# 06_PWM_IO.net
KiCad netlist of a schematic drawn in Altium Designer
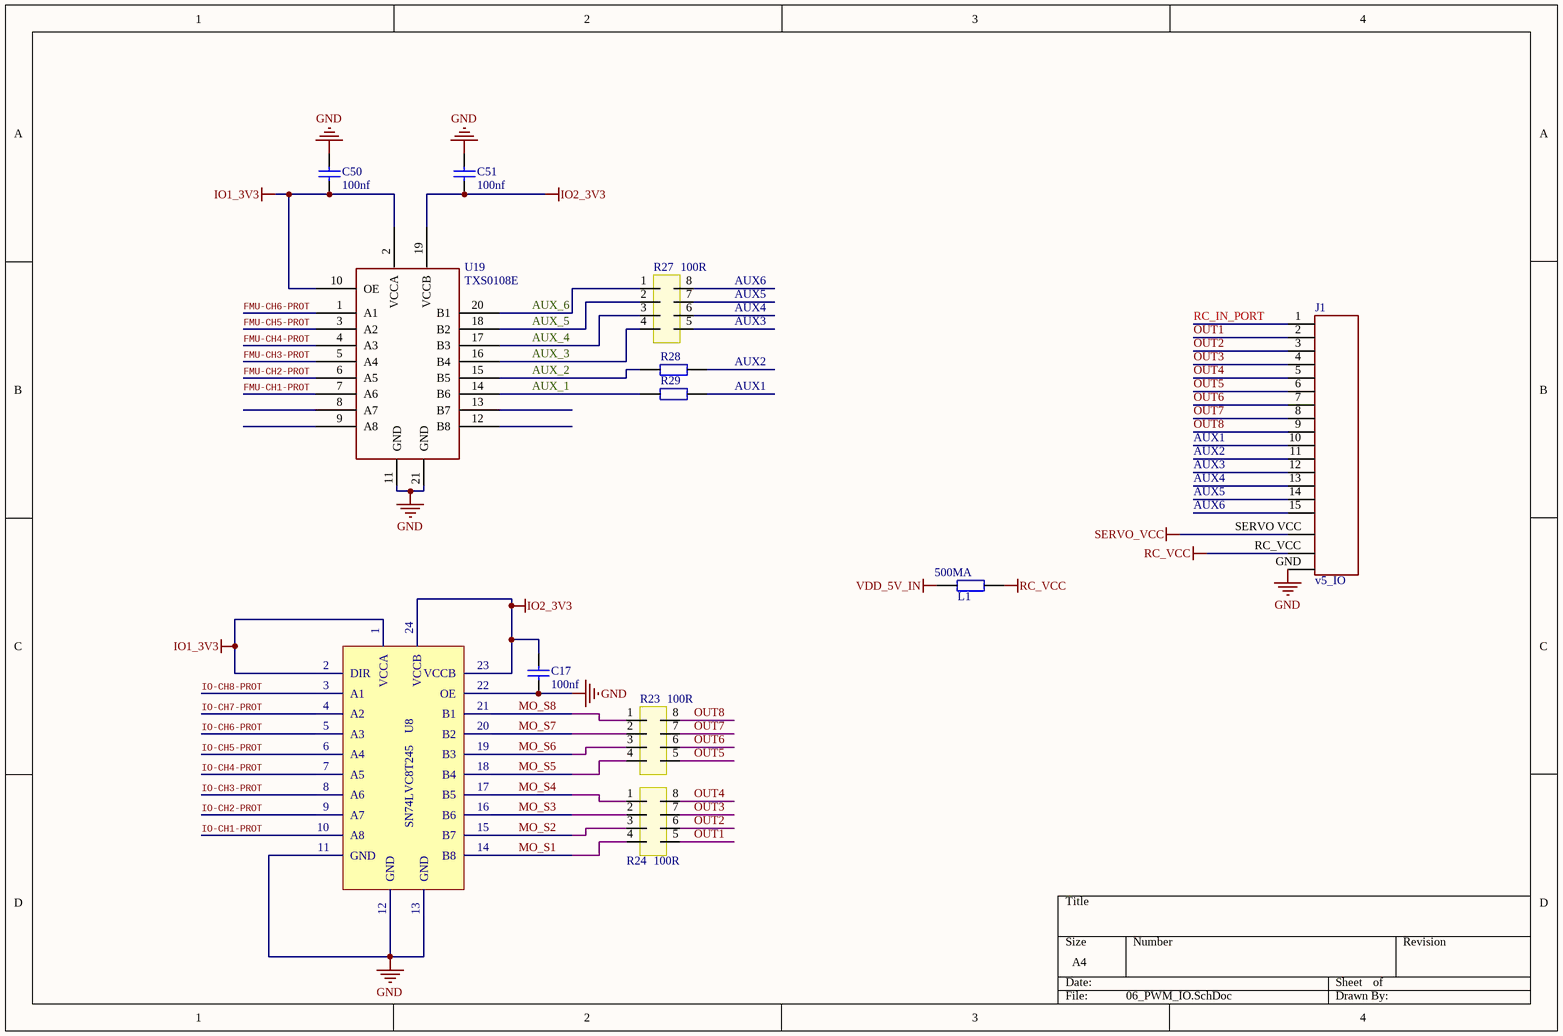
[diagram p0: 06_PWM_IO.SchDoc]

(export (version "E")
  (design (tool "Eeschema 10.0.6"))
  (components
    (comp (ref "C17")
      (value "100nf")
      (fields (field (name "PUBLISHER") "Altium Limited"))
      (libsource (lib "Miscellaneous Devices") (part "Cap"))
    )
    (comp (ref "C50") (value "100nf") (libsource (lib "Miscellaneous Devices") (part "Cap")))
    (comp (ref "C51") (value "100nf") (libsource (lib "Miscellaneous Devices") (part "Cap")))
    (comp (ref "J1") (value "v5_IO") (footprint "V5_IO_PWM") (libsource (lib "CUAV") (part "v5_IO")))
    (comp (ref "L1")
      (value "500MA")
      (footprint "0805l")
      (description "0402R100R 1%")
      (libsource (lib "CUAV") (part "0402R100R"))
    )
    (comp (ref "R23") (value "100R") (footprint "0402_4r") (libsource (lib "CUAV") (part "0402-8R-4R")))
    (comp (ref "R24") (value "100R") (footprint "0402_4r") (libsource (lib "CUAV") (part "0402-8R-4R")))
    (comp (ref "R27") (value "100R") (footprint "0402_4r") (libsource (lib "CUAV") (part "0402-8R-4R")))
    (comp (ref "R28")
      (value "0402R100R")
      (footprint "0402R")
      (description "0402R100R 1%")
      (libsource (lib "") (part "0402R100R_1"))
    )
    (comp (ref "R29")
      (value "0402R100R")
      (footprint "0402R")
      (description "0402R100R 1%")
      (libsource (lib "") (part "0402R100R_1"))
    )
    (comp (ref "U8")
      (value "SN74LVC8T245")
      (footprint "QFN24-RGY")
      (libsource (lib "CUAV") (part "SN74LVC8T245"))
    )
    (comp (ref "U19") (value "TXS0108E") (footprint "VQFN20") (libsource (lib "CUAV") (part "TXS0108E")))
  )
  (nets
    (net (code "1") (name "/AUX1") (class "Default")
      (node (ref "J1") (pin "10") (pintype "passive"))
      (node (ref "R29") (pin "2") (pintype "passive"))
    )
    (net (code "2") (name "/AUX2") (class "Default")
      (node (ref "J1") (pin "11") (pintype "passive"))
      (node (ref "R28") (pin "2") (pintype "passive"))
    )
    (net (code "3") (name "/AUX3") (class "Default")
      (node (ref "J1") (pin "12") (pintype "passive"))
      (node (ref "R27") (pin "5") (pinfunction "5_5") (pintype "passive"))
    )
    (net (code "4") (name "/AUX4") (class "Default")
      (node (ref "J1") (pin "13") (pintype "passive"))
      (node (ref "R27") (pin "6") (pinfunction "6_6") (pintype "passive"))
    )
    (net (code "5") (name "/AUX5") (class "Default")
      (node (ref "J1") (pin "14") (pintype "passive"))
      (node (ref "R27") (pin "7") (pinfunction "7_7") (pintype "passive"))
    )
    (net (code "6") (name "/AUX6") (class "Default")
      (node (ref "J1") (pin "15") (pintype "passive"))
      (node (ref "R27") (pin "8") (pinfunction "8_8") (pintype "passive"))
    )
    (net (code "7") (name "/AUX_1") (class "Default")
      (node (ref "R29") (pin "1") (pintype "passive"))
      (node (ref "U19") (pin "14") (pinfunction "B6_14") (pintype "passive"))
    )
    (net (code "8") (name "/AUX_2") (class "Default")
      (node (ref "R28") (pin "1") (pintype "passive"))
      (node (ref "U19") (pin "15") (pinfunction "B5_15") (pintype "passive"))
    )
    (net (code "9") (name "/AUX_3") (class "Default")
      (node (ref "R27") (pin "4") (pinfunction "4_4") (pintype "passive"))
      (node (ref "U19") (pin "16") (pinfunction "B4_16") (pintype "passive"))
    )
    (net (code "10") (name "/AUX_4") (class "Default")
      (node (ref "R27") (pin "3") (pinfunction "3_3") (pintype "passive"))
      (node (ref "U19") (pin "17") (pinfunction "B3_17") (pintype "passive"))
    )
    (net (code "11") (name "/AUX_5") (class "Default")
      (node (ref "R27") (pin "2") (pinfunction "2_2") (pintype "passive"))
      (node (ref "U19") (pin "18") (pinfunction "B2_18") (pintype "passive"))
    )
    (net (code "12") (name "/AUX_6") (class "Default")
      (node (ref "R27") (pin "1") (pinfunction "1_1") (pintype "passive"))
      (node (ref "U19") (pin "20") (pinfunction "B1_20") (pintype "passive"))
    )
    (net (code "13") (name "/FMU-CH1-PROT") (class "Default")
      (node (ref "U19") (pin "7") (pinfunction "A6_7") (pintype "passive"))
    )
    (net (code "14") (name "/FMU-CH2-PROT") (class "Default")
      (node (ref "U19") (pin "6") (pinfunction "A5_6") (pintype "passive"))
    )
    (net (code "15") (name "/FMU-CH3-PROT") (class "Default")
      (node (ref "U19") (pin "5") (pinfunction "A4_5") (pintype "passive"))
    )
    (net (code "16") (name "/FMU-CH4-PROT") (class "Default")
      (node (ref "U19") (pin "4") (pinfunction "A3_4") (pintype "passive"))
    )
    (net (code "17") (name "/FMU-CH5-PROT") (class "Default")
      (node (ref "U19") (pin "3") (pinfunction "A2_3") (pintype "passive"))
    )
    (net (code "18") (name "/FMU-CH6-PROT") (class "Default")
      (node (ref "U19") (pin "1") (pinfunction "A1_1") (pintype "passive"))
    )
    (net (code "19") (name "/IO-CH1-PROT") (class "Default")
      (node (ref "U8") (pin "10") (pinfunction "A8_10") (pintype "passive"))
    )
    (net (code "20") (name "/IO-CH2-PROT") (class "Default")
      (node (ref "U8") (pin "9") (pinfunction "A7_9") (pintype "passive"))
    )
    (net (code "21") (name "/IO-CH3-PROT") (class "Default")
      (node (ref "U8") (pin "8") (pinfunction "A6_8") (pintype "passive"))
    )
    (net (code "22") (name "/IO-CH4-PROT") (class "Default")
      (node (ref "U8") (pin "7") (pinfunction "A5_7") (pintype "passive"))
    )
    (net (code "23") (name "/IO-CH5-PROT") (class "Default")
      (node (ref "U8") (pin "6") (pinfunction "A4_6") (pintype "passive"))
    )
    (net (code "24") (name "/IO-CH6-PROT") (class "Default")
      (node (ref "U8") (pin "5") (pinfunction "A3_5") (pintype "passive"))
    )
    (net (code "25") (name "/IO-CH7-PROT") (class "Default")
      (node (ref "U8") (pin "4") (pinfunction "A2_4") (pintype "passive"))
    )
    (net (code "26") (name "/IO-CH8-PROT") (class "Default")
      (node (ref "U8") (pin "3") (pinfunction "A1_3") (pintype "passive"))
    )
    (net (code "27") (name "/MO_S1") (class "Default")
      (node (ref "R24") (pin "4") (pinfunction "4_4") (pintype "passive"))
      (node (ref "U8") (pin "14") (pinfunction "B8_14") (pintype "passive"))
    )
    (net (code "28") (name "/MO_S2") (class "Default")
      (node (ref "R24") (pin "3") (pinfunction "3_3") (pintype "passive"))
      (node (ref "U8") (pin "15") (pinfunction "B7_15") (pintype "passive"))
    )
    (net (code "29") (name "/MO_S3") (class "Default")
      (node (ref "R24") (pin "2") (pinfunction "2_2") (pintype "passive"))
      (node (ref "U8") (pin "16") (pinfunction "B6_16") (pintype "passive"))
    )
    (net (code "30") (name "/MO_S4") (class "Default")
      (node (ref "R24") (pin "1") (pinfunction "1_1") (pintype "passive"))
      (node (ref "U8") (pin "17") (pinfunction "B5_17") (pintype "passive"))
    )
    (net (code "31") (name "/MO_S5") (class "Default")
      (node (ref "R23") (pin "4") (pinfunction "4_4") (pintype "passive"))
      (node (ref "U8") (pin "18") (pinfunction "B4_18") (pintype "passive"))
    )
    (net (code "32") (name "/MO_S6") (class "Default")
      (node (ref "R23") (pin "3") (pinfunction "3_3") (pintype "passive"))
      (node (ref "U8") (pin "19") (pinfunction "B3_19") (pintype "passive"))
    )
    (net (code "33") (name "/MO_S7") (class "Default")
      (node (ref "R23") (pin "2") (pinfunction "2_2") (pintype "passive"))
      (node (ref "U8") (pin "20") (pinfunction "B2_20") (pintype "passive"))
    )
    (net (code "34") (name "/MO_S8") (class "Default")
      (node (ref "R23") (pin "1") (pinfunction "1_1") (pintype "passive"))
      (node (ref "U8") (pin "21") (pinfunction "B1_21") (pintype "passive"))
    )
    (net (code "35") (name "/OUT1") (class "Default")
      (node (ref "J1") (pin "2") (pintype "passive"))
      (node (ref "R24") (pin "5") (pinfunction "5_5") (pintype "passive"))
    )
    (net (code "36") (name "/OUT2") (class "Default")
      (node (ref "J1") (pin "3") (pintype "passive"))
      (node (ref "R24") (pin "6") (pinfunction "6_6") (pintype "passive"))
    )
    (net (code "37") (name "/OUT3") (class "Default")
      (node (ref "J1") (pin "4") (pintype "passive"))
      (node (ref "R24") (pin "7") (pinfunction "7_7") (pintype "passive"))
    )
    (net (code "38") (name "/OUT4") (class "Default")
      (node (ref "J1") (pin "5") (pintype "passive"))
      (node (ref "R24") (pin "8") (pinfunction "8_8") (pintype "passive"))
    )
    (net (code "39") (name "/OUT5") (class "Default")
      (node (ref "J1") (pin "6") (pintype "passive"))
      (node (ref "R23") (pin "5") (pinfunction "5_5") (pintype "passive"))
    )
    (net (code "40") (name "/OUT6") (class "Default")
      (node (ref "J1") (pin "7") (pintype "passive"))
      (node (ref "R23") (pin "6") (pinfunction "6_6") (pintype "passive"))
    )
    (net (code "41") (name "/OUT7") (class "Default")
      (node (ref "J1") (pin "8") (pintype "passive"))
      (node (ref "R23") (pin "7") (pinfunction "7_7") (pintype "passive"))
    )
    (net (code "42") (name "/OUT8") (class "Default")
      (node (ref "J1") (pin "9") (pintype "passive"))
      (node (ref "R23") (pin "8") (pinfunction "8_8") (pintype "passive"))
    )
    (net (code "43") (name "/RC_IN_PORT") (class "Default") (node (ref "J1") (pin "1") (pintype "passive")))
    (net (code "44") (name "GND") (class "Default")
      (node (ref "C17") (pin "1") (pinfunction "1_1") (pintype "passive"))
      (node (ref "C50") (pin "1") (pinfunction "1_1") (pintype "passive"))
      (node (ref "C51") (pin "1") (pinfunction "1_1") (pintype "passive"))
      (node (ref "J1") (pin "GND") (pintype "passive"))
      (node (ref "U19") (pin "11") (pinfunction "GND_11") (pintype "passive"))
      (node (ref "U19") (pin "21") (pinfunction "GND_21") (pintype "passive"))
      (node (ref "U8") (pin "11") (pinfunction "GND_11") (pintype "passive"))
      (node (ref "U8") (pin "12") (pinfunction "GND_12") (pintype "passive"))
      (node (ref "U8") (pin "13") (pinfunction "GND_13") (pintype "passive"))
      (node (ref "U8") (pin "22") (pinfunction "OE_22") (pintype "passive"))
    )
    (net (code "45") (name "IO1_3V3") (class "Default")
      (node (ref "C50") (pin "2") (pinfunction "2_2") (pintype "passive"))
      (node (ref "U19") (pin "10") (pinfunction "OE_10") (pintype "passive"))
      (node (ref "U19") (pin "2") (pinfunction "VCCA_2") (pintype "passive"))
      (node (ref "U8") (pin "1") (pinfunction "VCCA_1") (pintype "passive"))
      (node (ref "U8") (pin "2") (pinfunction "DIR_2") (pintype "passive"))
    )
    (net (code "46") (name "IO2_3V3") (class "Default")
      (node (ref "C17") (pin "2") (pinfunction "2_2") (pintype "passive"))
      (node (ref "C51") (pin "2") (pinfunction "2_2") (pintype "passive"))
      (node (ref "U19") (pin "19") (pinfunction "VCCB_19") (pintype "passive"))
      (node (ref "U8") (pin "23") (pinfunction "VCCB_23") (pintype "passive"))
      (node (ref "U8") (pin "24") (pinfunction "VCCB_24") (pintype "passive"))
    )
    (net (code "47") (name "RC_VCC") (class "Default")
      (node (ref "J1") (pin "RC_VCC") (pintype "passive"))
      (node (ref "L1") (pin "1") (pintype "passive"))
    )
    (net (code "48") (name "SERVO_VCC") (class "Default")
      (node (ref "J1") (pin "SERVO_VCC") (pintype "passive"))
    )
    (net (code "49") (name "VDD_5V_IN") (class "Default") (node (ref "L1") (pin "2") (pintype "passive")))
    (net (code "50") (name "unconnected-(U19-A7-Pad8)") (class "Default")
      (node (ref "U19") (pin "8") (pinfunction "A7_8") (pintype "passive"))
    )
    (net (code "51") (name "unconnected-(U19-A8-Pad9)") (class "Default")
      (node (ref "U19") (pin "9") (pinfunction "A8_9") (pintype "passive"))
    )
    (net (code "52") (name "unconnected-(U19-B7-Pad13)") (class "Default")
      (node (ref "U19") (pin "13") (pinfunction "B7_13") (pintype "passive"))
    )
    (net (code "53") (name "unconnected-(U19-B8-Pad12)") (class "Default")
      (node (ref "U19") (pin "12") (pinfunction "B8_12") (pintype "passive"))
    )
  )
)
